# AdamOBrien_IOT2_PicController.net
KiCad netlist of a schematic drawn in EAGLE
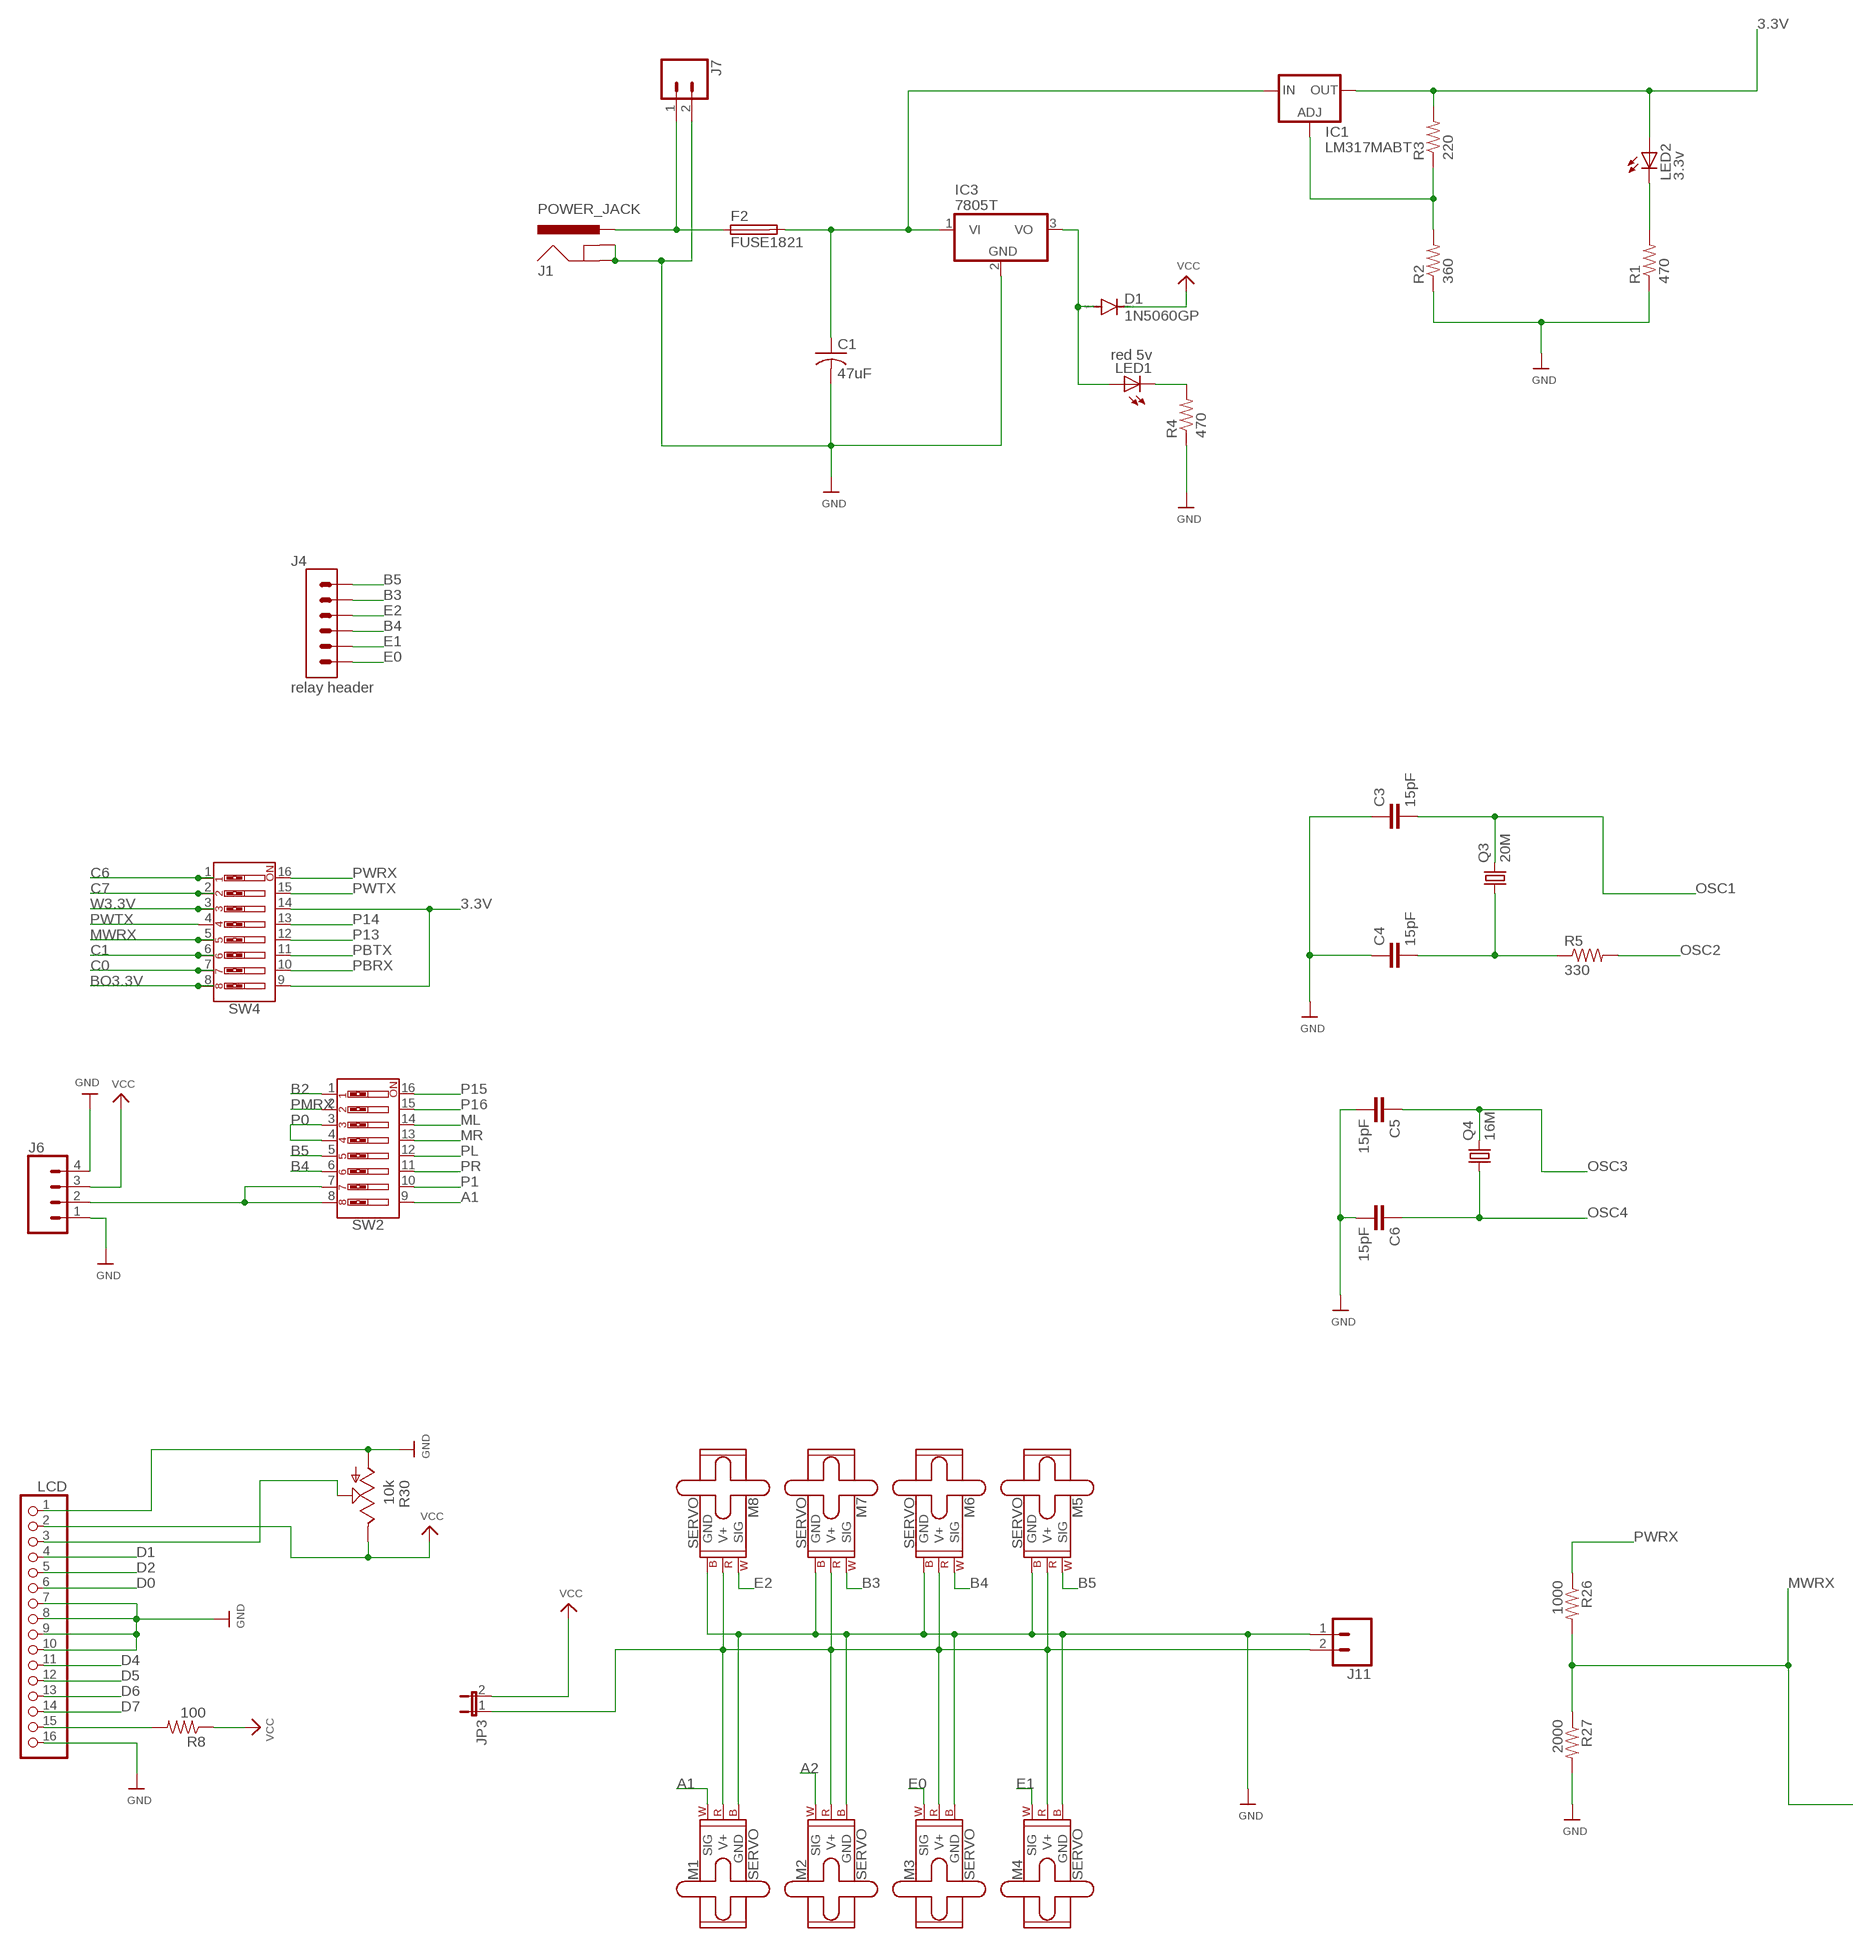
[diagram p0: schematic, sheet 1, part 1 of 2]
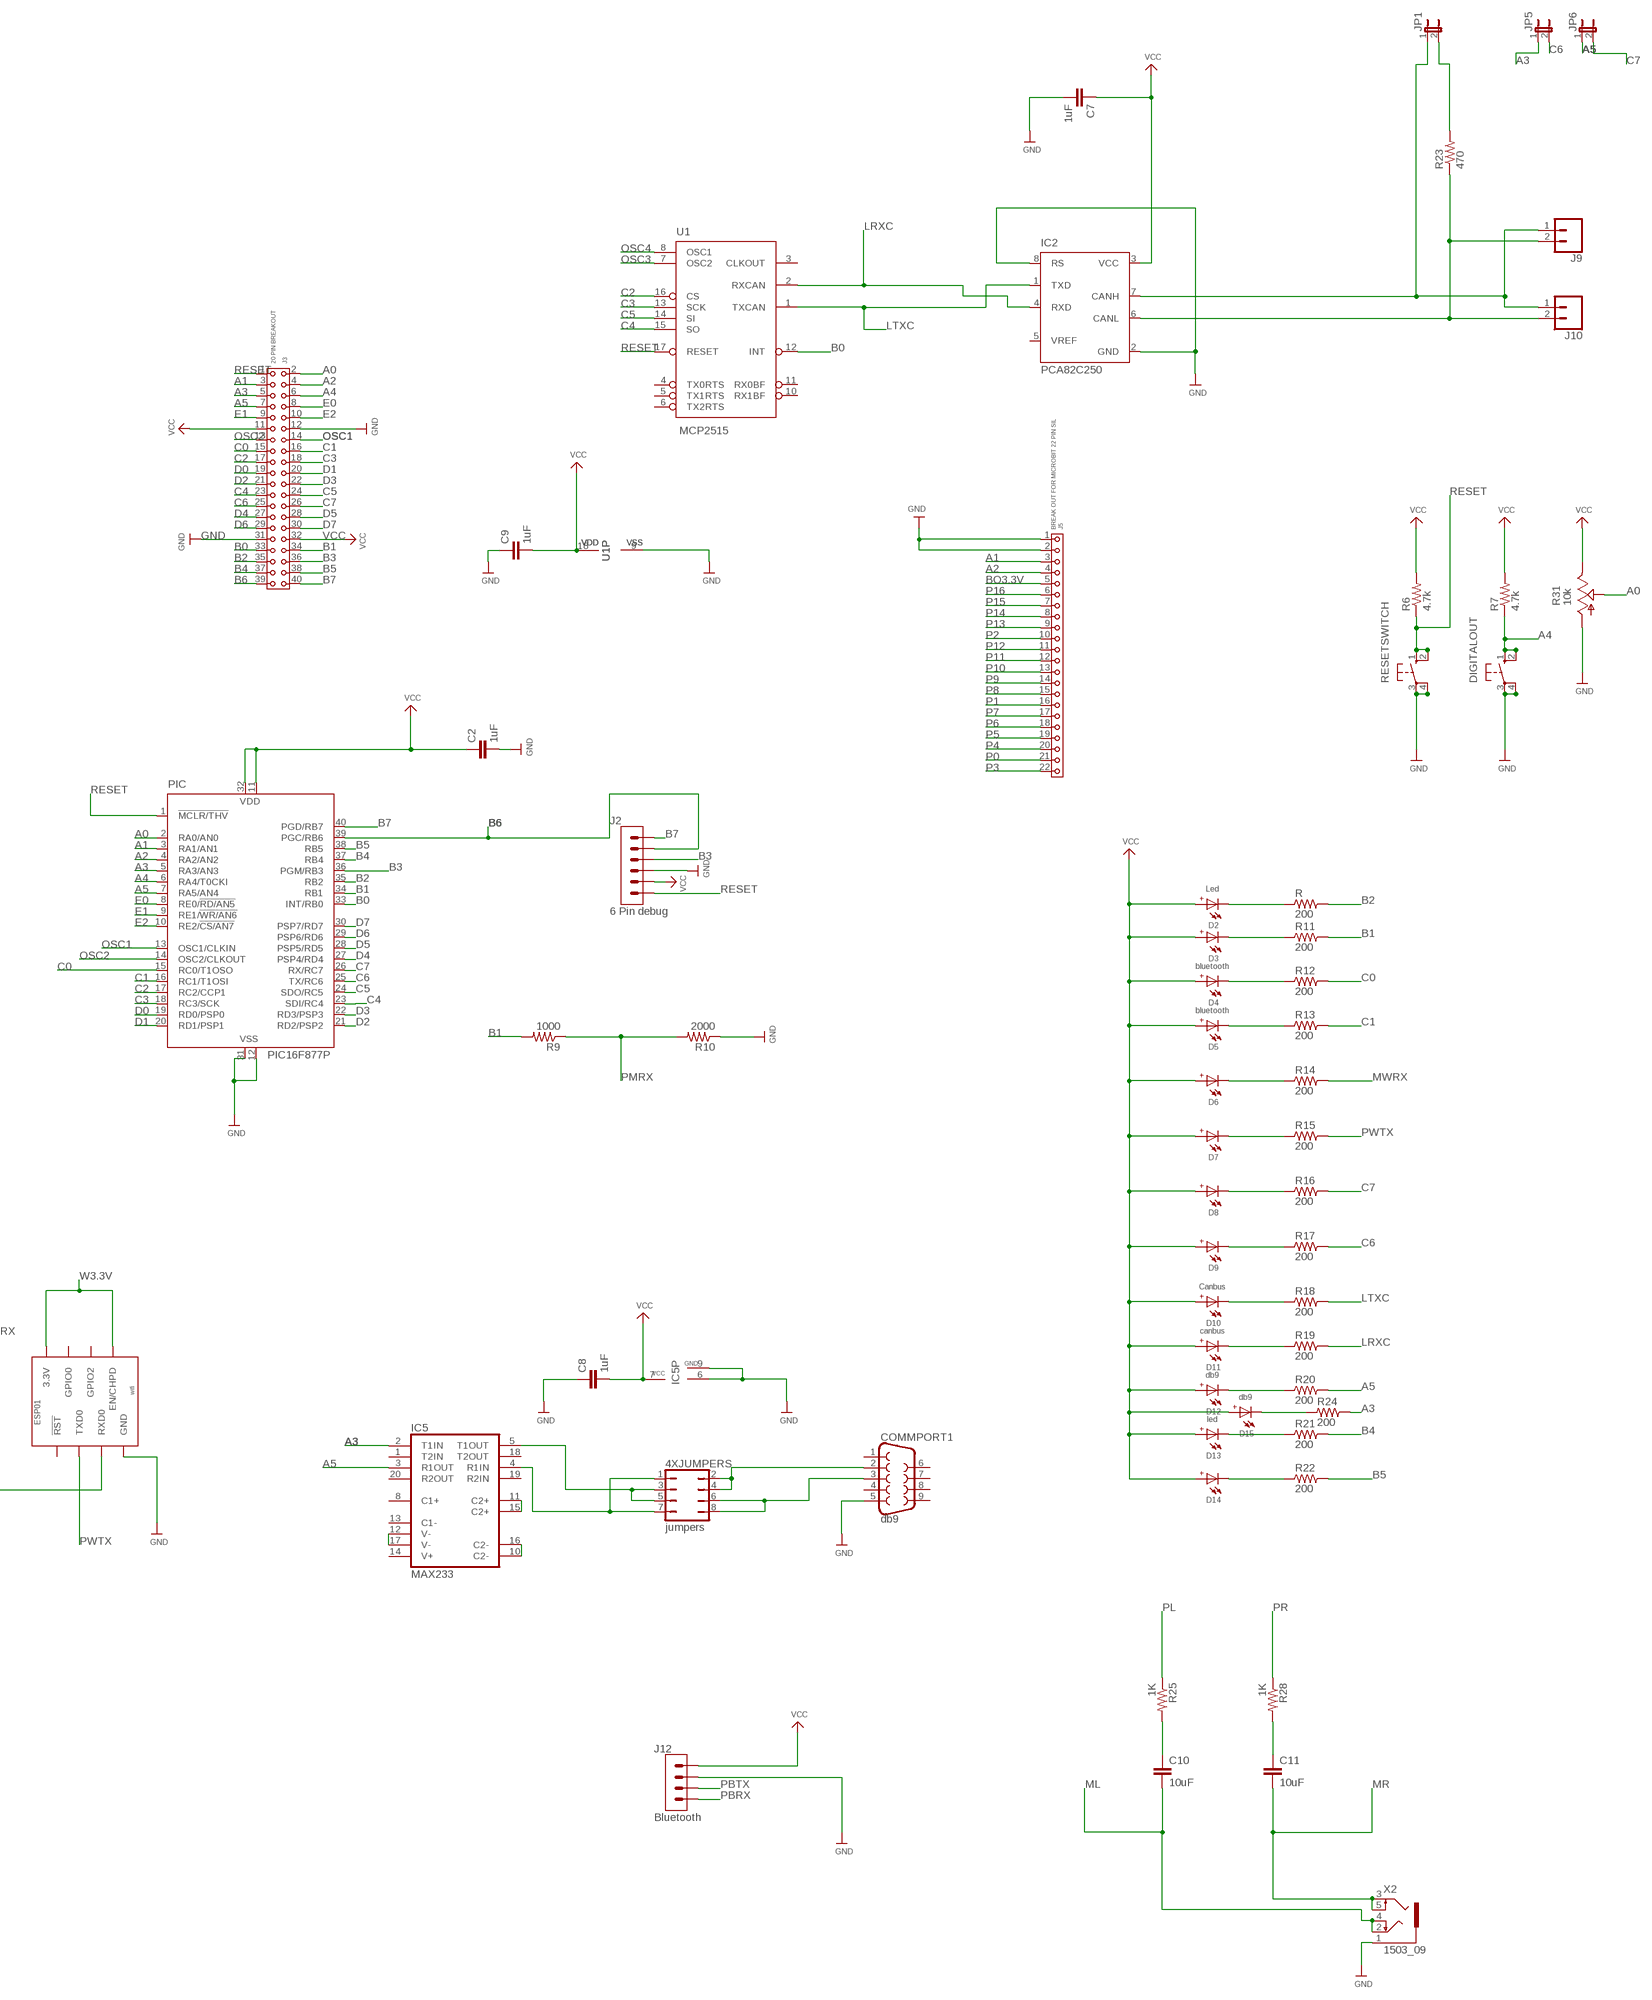
[diagram p1: schematic, sheet 1, part 2 of 2]

(export (version "E")
  (design (tool "Eeschema 10.0.6"))
  (components
    (comp (ref "4XJUMPERS")
      (value "jumpers")
      (footprint "eagle-import:JP4Q")
      (libsource (lib "eagle-import") (part "JP4Q"))
    )
    (comp (ref "C1")
      (value "47uF")
      (footprint "eagle-import:C025-024X044")
      (libsource (lib "eagle-import") (part "C-US025-024X044"))
    )
    (comp (ref "C2")
      (value "1uF")
      (footprint "eagle-import:C2.5-2")
      (libsource (lib "eagle-import") (part "C2.5/2"))
    )
    (comp (ref "C3")
      (value "15pF")
      (footprint "eagle-import:C2.5-2")
      (libsource (lib "eagle-import") (part "C2.5/2"))
    )
    (comp (ref "C4")
      (value "15pF")
      (footprint "eagle-import:C2.5-2")
      (libsource (lib "eagle-import") (part "C2.5/2"))
    )
    (comp (ref "C5")
      (value "15pF")
      (footprint "eagle-import:C2.5-2")
      (libsource (lib "eagle-import") (part "C2.5/2"))
    )
    (comp (ref "C6")
      (value "15pF")
      (footprint "eagle-import:C2.5-2")
      (libsource (lib "eagle-import") (part "C2.5/2"))
    )
    (comp (ref "C7")
      (value "1uF")
      (footprint "eagle-import:C2.5-2")
      (libsource (lib "eagle-import") (part "C2.5/2"))
    )
    (comp (ref "C8")
      (value "1uF")
      (footprint "eagle-import:C2.5-2")
      (libsource (lib "eagle-import") (part "C2.5/2"))
    )
    (comp (ref "C9")
      (value "1uF")
      (footprint "eagle-import:C2.5-2")
      (libsource (lib "eagle-import") (part "C2.5/2"))
    )
    (comp (ref "C10")
      (value "10uF")
      (footprint "eagle-import:C2.5-2")
      (libsource (lib "eagle-import") (part "C2.5/2"))
    )
    (comp (ref "C11")
      (value "10uF")
      (footprint "eagle-import:C2.5-2")
      (libsource (lib "eagle-import") (part "C2.5/2"))
    )
    (comp (ref "COMMPORT1")
      (value "db9")
      (footprint "eagle-import:DB9")
      (libsource (lib "eagle-import") (part "DB9FEMALE"))
    )
    (comp (ref "D1")
      (value "1N5060GP")
      (footprint "eagle-import:DO15-12")
      (libsource (lib "eagle-import") (part "1N5060GP"))
    )
    (comp (ref "D2")
      (value "Led")
      (footprint "eagle-import:WL-SITW_3528")
      (libsource (lib "eagle-import") (part "WL-SITW_3528_15414185BA210"))
    )
    (comp (ref "D3")
      (value "WL-SITW_3528_15414185BA210")
      (footprint "eagle-import:WL-SITW_3528")
      (libsource (lib "eagle-import") (part "WL-SITW_3528_15414185BA210"))
    )
    (comp (ref "D4")
      (value "bluetooth")
      (footprint "eagle-import:WL-SITW_3528")
      (libsource (lib "eagle-import") (part "WL-SITW_3528_15414185BA210"))
    )
    (comp (ref "D5")
      (value "bluetooth")
      (footprint "eagle-import:WL-SITW_3528")
      (libsource (lib "eagle-import") (part "WL-SITW_3528_15414185BA210"))
    )
    (comp (ref "D6")
      (value "WL-SITW_3528_15414185BA210")
      (footprint "eagle-import:WL-SITW_3528")
      (libsource (lib "eagle-import") (part "WL-SITW_3528_15414185BA210"))
    )
    (comp (ref "D7")
      (value "WL-SITW_3528_15414185BA210")
      (footprint "eagle-import:WL-SITW_3528")
      (libsource (lib "eagle-import") (part "WL-SITW_3528_15414185BA210"))
    )
    (comp (ref "D8")
      (value "WL-SITW_3528_15414185BA210")
      (footprint "eagle-import:WL-SITW_3528")
      (libsource (lib "eagle-import") (part "WL-SITW_3528_15414185BA210"))
    )
    (comp (ref "D9")
      (value "WL-SITW_3528_15414185BA210")
      (footprint "eagle-import:WL-SITW_3528")
      (libsource (lib "eagle-import") (part "WL-SITW_3528_15414185BA210"))
    )
    (comp (ref "D10")
      (value "Canbus")
      (footprint "eagle-import:WL-SITW_3528")
      (libsource (lib "eagle-import") (part "WL-SITW_3528_15414185BA210"))
    )
    (comp (ref "D11")
      (value "canbus")
      (footprint "eagle-import:WL-SITW_3528")
      (libsource (lib "eagle-import") (part "WL-SITW_3528_15414185BA210"))
    )
    (comp (ref "D12")
      (value "db9")
      (footprint "eagle-import:WL-SITW_3528")
      (libsource (lib "eagle-import") (part "WL-SITW_3528_15414185BA210"))
    )
    (comp (ref "D13")
      (value "led")
      (footprint "eagle-import:WL-SITW_3528")
      (libsource (lib "eagle-import") (part "WL-SITW_3528_15414185BA210"))
    )
    (comp (ref "D14")
      (value "WL-SITW_3528_15414185BA210")
      (footprint "eagle-import:WL-SITW_3528")
      (libsource (lib "eagle-import") (part "WL-SITW_3528_15414185BA210"))
    )
    (comp (ref "D15")
      (value "db9")
      (footprint "eagle-import:WL-SITW_3528")
      (libsource (lib "eagle-import") (part "WL-SITW_3528_15414185BA210"))
    )
    (comp (ref "DIGITALOUT")
      (value "10-XX")
      (footprint "eagle-import:B3F-10XX")
      (fields (field (name "MPN") "B3F-1000"))
      (libsource (lib "eagle-import") (part "10-XX"))
    )
    (comp (ref "ESP01")
      (value "wifi")
      (footprint "eagle-import:ESP8266_ESP-01_NO-SILKSCREEN")
      (libsource (lib "eagle-import") (part "ESP8266_ESP-?01"))
    )
    (comp (ref "F2")
      (value "FUSE1821")
      (footprint "eagle-import:FUSE_HOLDER_MENTOR-1821")
      (libsource (lib "eagle-import") (part "FUSE1821"))
    )
    (comp (ref "IC1")
      (value "LM317MABT")
      (footprint "eagle-import:TO220L1")
      (libsource (lib "eagle-import") (part "LM317?MABT"))
    )
    (comp (ref "IC2")
      (value "PCA82C250")
      (footprint "eagle-import:DIL08")
      (libsource (lib "eagle-import") (part "PCA82C250"))
    )
    (comp (ref "IC3")
      (value "7805T")
      (footprint "eagle-import:TO220H")
      (libsource (lib "eagle-import") (part "78T05"))
    )
    (comp (ref "IC5")
      (value "MAX233")
      (footprint "eagle-import:DIL20")
      (fields (field (name "MPN") "MAX233ACPP+G36"))
      (libsource (lib "eagle-import") (part "MAX233"))
    )
    (comp (ref "J1")
      (value "POWER_JACK")
      (footprint "eagle-import:POWER_JACK_PTH")
      (libsource (lib "eagle-import") (part "POWER_JACK"))
    )
    (comp (ref "J2")
      (value "6 Pin debug")
      (footprint "eagle-import:62000611121")
      (fields
        (field (name "MANUFACTURER") "Würth Elektronik ")
        (field (name "MPN") "62000611121")
        (field (name "CREATED_BY") "PCBLayout.com")
      )
      (libsource (lib "eagle-import") (part "62000611121"))
    )
    (comp (ref "J3")
      (value "20 PIN BREAKOUT")
      (footprint "eagle-import:61304021821")
      (libsource (lib "eagle-import") (part "6130XX21821_61304021821"))
    )
    (comp (ref "J4")
      (value "relay header")
      (footprint "eagle-import:62000611121")
      (fields
        (field (name "MANUFACTURER") "Würth Elektronik ")
        (field (name "MPN") "62000611121")
        (field (name "CREATED_BY") "PCBLayout.com")
      )
      (libsource (lib "eagle-import") (part "62000611121"))
    )
    (comp (ref "J5")
      (value "BREAK OUT FOR MICROBIT 22 PIN SIL")
      (footprint "eagle-import:61302211821")
      (libsource (lib "eagle-import") (part "6130XX11821_61302211821"))
    )
    (comp (ref "J6")
      (value "CONN_04")
      (footprint "eagle-import:1X04")
      (libsource (lib "eagle-import") (part "CONN_04"))
    )
    (comp (ref "J7")
      (value "CONN_025MM")
      (footprint "eagle-import:SCREWTERMINAL-5MM-2")
      (libsource (lib "eagle-import") (part "CONN_025MM"))
    )
    (comp (ref "J9")
      (value "CONN_025MM")
      (footprint "eagle-import:SCREWTERMINAL-5MM-2")
      (libsource (lib "eagle-import") (part "CONN_025MM"))
    )
    (comp (ref "J10")
      (value "CONN_025MM")
      (footprint "eagle-import:SCREWTERMINAL-5MM-2")
      (libsource (lib "eagle-import") (part "CONN_025MM"))
    )
    (comp (ref "J11")
      (value "CONN_025MM")
      (footprint "eagle-import:SCREWTERMINAL-5MM-2")
      (libsource (lib "eagle-import") (part "CONN_025MM"))
    )
    (comp (ref "J12")
      (value "Bluetooth")
      (footprint "eagle-import:62000411121")
      (fields
        (field (name "MANUFACTURER") "Würth Elektronik ")
        (field (name "MPN") "62000411121")
        (field (name "CREATED_BY") "PCBLayout.com")
      )
      (libsource (lib "eagle-import") (part "62000411121"))
    )
    (comp (ref "JP1")
      (value "JP1E")
      (footprint "eagle-import:JP1")
      (libsource (lib "eagle-import") (part "JP1E"))
    )
    (comp (ref "JP3")
      (value "JP1E")
      (footprint "eagle-import:JP1")
      (libsource (lib "eagle-import") (part "JP1E"))
    )
    (comp (ref "JP5")
      (value "JP1E")
      (footprint "eagle-import:JP1")
      (libsource (lib "eagle-import") (part "JP1E"))
    )
    (comp (ref "JP6")
      (value "JP1E")
      (footprint "eagle-import:JP1")
      (libsource (lib "eagle-import") (part "JP1E"))
    )
    (comp (ref "LCD")
      (value "PINHD-1X16")
      (footprint "eagle-import:1X16")
      (libsource (lib "eagle-import") (part "PINHD-1X16"))
    )
    (comp (ref "LED1")
      (value "red 5v")
      (footprint "eagle-import:LED5MM")
      (libsource (lib "eagle-import") (part "LED5MM"))
    )
    (comp (ref "LED2")
      (value "3.3v")
      (footprint "eagle-import:LED5MM")
      (libsource (lib "eagle-import") (part "LED5MM"))
    )
    (comp (ref "M1")
      (value "SERVO")
      (footprint "eagle-import:1X03")
      (libsource (lib "eagle-import") (part "SERVO"))
    )
    (comp (ref "M2")
      (value "SERVO")
      (footprint "eagle-import:1X03")
      (libsource (lib "eagle-import") (part "SERVO"))
    )
    (comp (ref "M3")
      (value "SERVO")
      (footprint "eagle-import:1X03")
      (libsource (lib "eagle-import") (part "SERVO"))
    )
    (comp (ref "M4")
      (value "SERVO")
      (footprint "eagle-import:1X03")
      (libsource (lib "eagle-import") (part "SERVO"))
    )
    (comp (ref "M5")
      (value "SERVO")
      (footprint "eagle-import:1X03")
      (libsource (lib "eagle-import") (part "SERVO"))
    )
    (comp (ref "M6")
      (value "SERVO")
      (footprint "eagle-import:1X03")
      (libsource (lib "eagle-import") (part "SERVO"))
    )
    (comp (ref "M7")
      (value "SERVO")
      (footprint "eagle-import:1X03")
      (libsource (lib "eagle-import") (part "SERVO"))
    )
    (comp (ref "M8")
      (value "SERVO")
      (footprint "eagle-import:1X03")
      (libsource (lib "eagle-import") (part "SERVO"))
    )
    (comp (ref "PIC")
      (value "PIC16F877P")
      (footprint "eagle-import:DIL40")
      (fields (field (name "MF") "MICROCHIP") (field (name "MPN") "PIC16F877-04/P"))
      (libsource (lib "eagle-import") (part "PIC16F87P7"))
    )
    (comp (ref "Q3")
      (value "20M")
      (footprint "eagle-import:HC49_S")
      (libsource (lib "eagle-import") (part "CRYSTALHC49S"))
    )
    (comp (ref "Q4")
      (value "16M")
      (footprint "eagle-import:HC49_S")
      (libsource (lib "eagle-import") (part "CRYSTALHC49S"))
    )
    (comp (ref "R")
      (value "200")
      (footprint "eagle-import:RC-MASTER-SMD_R1206MP")
      (libsource (lib "eagle-import") (part "RC-MASTER-SMD_R_1206MP"))
    )
    (comp (ref "R1")
      (value "470")
      (footprint "eagle-import:0204_7")
      (libsource (lib "eagle-import") (part "R-US_0204/7"))
    )
    (comp (ref "R2")
      (value "360")
      (footprint "eagle-import:0204_7")
      (libsource (lib "eagle-import") (part "R-US_0204/7"))
    )
    (comp (ref "R3")
      (value "220")
      (footprint "eagle-import:0204_7")
      (libsource (lib "eagle-import") (part "R-US_0204/7"))
    )
    (comp (ref "R4")
      (value "470")
      (footprint "eagle-import:0204_7")
      (libsource (lib "eagle-import") (part "R-US_0204/7"))
    )
    (comp (ref "R5")
      (value "330")
      (footprint "eagle-import:0204_7")
      (libsource (lib "eagle-import") (part "R-US_0204/7"))
    )
    (comp (ref "R6")
      (value "4.7k")
      (footprint "eagle-import:0204_7")
      (libsource (lib "eagle-import") (part "R-US_0204/7"))
    )
    (comp (ref "R7")
      (value "4.7k")
      (footprint "eagle-import:0204_7")
      (libsource (lib "eagle-import") (part "R-US_0204/7"))
    )
    (comp (ref "R8")
      (value "100")
      (footprint "eagle-import:0204_7")
      (libsource (lib "eagle-import") (part "R-US_0204/7"))
    )
    (comp (ref "R9")
      (value "1000")
      (footprint "eagle-import:0204_7")
      (libsource (lib "eagle-import") (part "R-US_0204/7"))
    )
    (comp (ref "R10")
      (value "2000")
      (footprint "eagle-import:0204_7")
      (libsource (lib "eagle-import") (part "R-US_0204/7"))
    )
    (comp (ref "R11")
      (value "200")
      (footprint "eagle-import:RC-MASTER-SMD_R1206MP")
      (libsource (lib "eagle-import") (part "RC-MASTER-SMD_R_1206MP"))
    )
    (comp (ref "R12")
      (value "200")
      (footprint "eagle-import:RC-MASTER-SMD_R1206MP")
      (libsource (lib "eagle-import") (part "RC-MASTER-SMD_R_1206MP"))
    )
    (comp (ref "R13")
      (value "200")
      (footprint "eagle-import:RC-MASTER-SMD_R1206MP")
      (libsource (lib "eagle-import") (part "RC-MASTER-SMD_R_1206MP"))
    )
    (comp (ref "R14")
      (value "200")
      (footprint "eagle-import:RC-MASTER-SMD_R1206MP")
      (libsource (lib "eagle-import") (part "RC-MASTER-SMD_R_1206MP"))
    )
    (comp (ref "R15")
      (value "200")
      (footprint "eagle-import:RC-MASTER-SMD_R1206MP")
      (libsource (lib "eagle-import") (part "RC-MASTER-SMD_R_1206MP"))
    )
    (comp (ref "R16")
      (value "200")
      (footprint "eagle-import:RC-MASTER-SMD_R1206MP")
      (libsource (lib "eagle-import") (part "RC-MASTER-SMD_R_1206MP"))
    )
    (comp (ref "R17")
      (value "200")
      (footprint "eagle-import:RC-MASTER-SMD_R1206MP")
      (libsource (lib "eagle-import") (part "RC-MASTER-SMD_R_1206MP"))
    )
    (comp (ref "R18")
      (value "200")
      (footprint "eagle-import:RC-MASTER-SMD_R1206MP")
      (libsource (lib "eagle-import") (part "RC-MASTER-SMD_R_1206MP"))
    )
    (comp (ref "R19")
      (value "200")
      (footprint "eagle-import:RC-MASTER-SMD_R1206MP")
      (libsource (lib "eagle-import") (part "RC-MASTER-SMD_R_1206MP"))
    )
    (comp (ref "R20")
      (value "200")
      (footprint "eagle-import:RC-MASTER-SMD_R1206MP")
      (libsource (lib "eagle-import") (part "RC-MASTER-SMD_R_1206MP"))
    )
    (comp (ref "R21")
      (value "200")
      (footprint "eagle-import:RC-MASTER-SMD_R1206MP")
      (libsource (lib "eagle-import") (part "RC-MASTER-SMD_R_1206MP"))
    )
    (comp (ref "R22")
      (value "200")
      (footprint "eagle-import:RC-MASTER-SMD_R1206MP")
      (libsource (lib "eagle-import") (part "RC-MASTER-SMD_R_1206MP"))
    )
    (comp (ref "R23")
      (value "470")
      (footprint "eagle-import:0204_7")
      (libsource (lib "eagle-import") (part "R-US_0204/7"))
    )
    (comp (ref "R24")
      (value "200")
      (footprint "eagle-import:RC-MASTER-SMD_R1206MP")
      (libsource (lib "eagle-import") (part "RC-MASTER-SMD_R_1206MP"))
    )
    (comp (ref "R25")
      (value "1K")
      (footprint "eagle-import:0204_7")
      (libsource (lib "eagle-import") (part "R-US_0204/7"))
    )
    (comp (ref "R26")
      (value "1000")
      (footprint "eagle-import:0204_7")
      (libsource (lib "eagle-import") (part "R-US_0204/7"))
    )
    (comp (ref "R27")
      (value "2000")
      (footprint "eagle-import:0204_7")
      (libsource (lib "eagle-import") (part "R-US_0204/7"))
    )
    (comp (ref "R28")
      (value "1K")
      (footprint "eagle-import:0204_7")
      (libsource (lib "eagle-import") (part "R-US_0204/7"))
    )
    (comp (ref "R30")
      (value "10k")
      (footprint "eagle-import:RS3")
      (libsource (lib "eagle-import") (part "TRIM_US-RS3"))
    )
    (comp (ref "R31")
      (value "10k")
      (footprint "eagle-import:RS3")
      (libsource (lib "eagle-import") (part "TRIM_US-RS3"))
    )
    (comp (ref "RESETSWITCH")
      (value "10-XX")
      (footprint "eagle-import:B3F-10XX")
      (fields (field (name "MPN") "B3F-1000"))
      (libsource (lib "eagle-import") (part "10-XX"))
    )
    (comp (ref "SW2")
      (value "DIP-08-PTH")
      (footprint "eagle-import:DIPSWITCH-08")
      (libsource (lib "eagle-import") (part "DIP-08-PTH"))
    )
    (comp (ref "SW4")
      (value "DIP-08-PTH")
      (footprint "eagle-import:DIPSWITCH-08")
      (libsource (lib "eagle-import") (part "DIP-08-PTH"))
    )
    (comp (ref "U1")
      (value "MCP2515")
      (footprint "eagle-import:DIP18")
      (libsource (lib "eagle-import") (part "MCP2515(MCP2510)P"))
    )
    (comp (ref "X2")
      (value "1503_09")
      (footprint "eagle-import:1503_09")
      (libsource (lib "eagle-import") (part "1503_09"))
    )
  )
  (nets
    (net (code "1") (name "3.3V") (class "Default")
      (node (ref "IC1") (pin "2") (pinfunction "OUT_2") (pintype "passive"))
      (node (ref "LED2") (pin "A") (pinfunction "A_A") (pintype "passive"))
      (node (ref "R3") (pin "2") (pinfunction "2_2") (pintype "passive"))
      (node (ref "SW4") (pin "14") (pinfunction "14_14") (pintype "passive"))
      (node (ref "SW4") (pin "9") (pinfunction "9_9") (pintype "passive"))
    )
    (net (code "2") (name "A0") (class "Default")
      (node (ref "J3") (pin "2") (pinfunction "2_2") (pintype "passive"))
      (node (ref "PIC") (pin "2") (pinfunction "RA0/AN0_2") (pintype "bidirectional"))
      (node (ref "R31") (pin "S") (pinfunction "S_S") (pintype "passive"))
    )
    (net (code "3") (name "A1") (class "Default")
      (node (ref "J3") (pin "3") (pinfunction "3_3") (pintype "passive"))
      (node (ref "J5") (pin "3") (pinfunction "3_3") (pintype "passive"))
      (node (ref "M1") (pin "1") (pinfunction "SIG_1") (pintype "bidirectional"))
      (node (ref "PIC") (pin "3") (pinfunction "RA1/AN1_3") (pintype "bidirectional"))
      (node (ref "SW2") (pin "9") (pinfunction "9_9") (pintype "passive"))
    )
    (net (code "4") (name "A2") (class "Default")
      (node (ref "J3") (pin "4") (pinfunction "4_4") (pintype "passive"))
      (node (ref "J5") (pin "4") (pinfunction "4_4") (pintype "passive"))
      (node (ref "M2") (pin "1") (pinfunction "SIG_1") (pintype "bidirectional"))
      (node (ref "PIC") (pin "4") (pinfunction "RA2/AN2_4") (pintype "bidirectional"))
    )
    (net (code "5") (name "A3") (class "Default")
      (node (ref "IC5") (pin "2") (pinfunction "T1IN_2") (pintype "input"))
      (node (ref "J3") (pin "5") (pinfunction "5_5") (pintype "passive"))
      (node (ref "JP5") (pin "1") (pinfunction "1_1") (pintype "passive"))
      (node (ref "PIC") (pin "5") (pinfunction "RA3/AN3_5") (pintype "bidirectional"))
      (node (ref "R24") (pin "2") (pinfunction "2_2") (pintype "passive"))
    )
    (net (code "6") (name "A4") (class "Default")
      (node (ref "DIGITALOUT") (pin "1") (pinfunction "S_1") (pintype "passive"))
      (node (ref "DIGITALOUT") (pin "2") (pinfunction "S1_2") (pintype "passive"))
      (node (ref "J3") (pin "6") (pinfunction "6_6") (pintype "passive"))
      (node (ref "PIC") (pin "6") (pinfunction "RA4/T0CKI_6") (pintype "bidirectional"))
      (node (ref "R7") (pin "1") (pinfunction "1_1") (pintype "passive"))
    )
    (net (code "7") (name "A5") (class "Default")
      (node (ref "IC5") (pin "3") (pinfunction "R1OUT_3") (pintype "output"))
      (node (ref "J3") (pin "7") (pinfunction "7_7") (pintype "passive"))
      (node (ref "JP6") (pin "1") (pinfunction "1_1") (pintype "passive"))
      (node (ref "PIC") (pin "7") (pinfunction "RA5/AN4_7") (pintype "bidirectional"))
      (node (ref "R20") (pin "2") (pinfunction "2_2") (pintype "passive"))
    )
    (net (code "8") (name "B0") (class "Default")
      (node (ref "J3") (pin "33") (pinfunction "33_33") (pintype "passive"))
      (node (ref "PIC") (pin "33") (pinfunction "INT/RB0_33") (pintype "bidirectional"))
      (node (ref "U1") (pin "12") (pinfunction "INT_12") (pintype "output"))
    )
    (net (code "9") (name "B1") (class "Default")
      (node (ref "J3") (pin "34") (pinfunction "34_34") (pintype "passive"))
      (node (ref "PIC") (pin "34") (pinfunction "RB1_34") (pintype "bidirectional"))
      (node (ref "R11") (pin "2") (pinfunction "2_2") (pintype "passive"))
      (node (ref "R9") (pin "2") (pinfunction "2_2") (pintype "passive"))
    )
    (net (code "10") (name "B2") (class "Default")
      (node (ref "J3") (pin "35") (pinfunction "35_35") (pintype "passive"))
      (node (ref "PIC") (pin "35") (pinfunction "RB2_35") (pintype "bidirectional"))
      (node (ref "R") (pin "2") (pinfunction "2_2") (pintype "passive"))
      (node (ref "SW2") (pin "1") (pinfunction "1_1") (pintype "passive"))
    )
    (net (code "11") (name "B3") (class "Default")
      (node (ref "J2") (pin "3") (pinfunction "3_3") (pintype "passive"))
      (node (ref "J3") (pin "36") (pinfunction "36_36") (pintype "passive"))
      (node (ref "J4") (pin "2") (pinfunction "2_2") (pintype "passive"))
      (node (ref "M7") (pin "1") (pinfunction "SIG_1") (pintype "bidirectional"))
      (node (ref "PIC") (pin "36") (pinfunction "PGM/RB3_36") (pintype "bidirectional"))
    )
    (net (code "12") (name "B4") (class "Default")
      (node (ref "J3") (pin "37") (pinfunction "37_37") (pintype "passive"))
      (node (ref "J4") (pin "4") (pinfunction "4_4") (pintype "passive"))
      (node (ref "M6") (pin "1") (pinfunction "SIG_1") (pintype "bidirectional"))
      (node (ref "PIC") (pin "37") (pinfunction "RB4_37") (pintype "bidirectional"))
      (node (ref "R21") (pin "2") (pinfunction "2_2") (pintype "passive"))
      (node (ref "SW2") (pin "6") (pinfunction "6_6") (pintype "passive"))
    )
    (net (code "13") (name "B5") (class "Default")
      (node (ref "J3") (pin "38") (pinfunction "38_38") (pintype "passive"))
      (node (ref "J4") (pin "1") (pinfunction "1_1") (pintype "passive"))
      (node (ref "M5") (pin "1") (pinfunction "SIG_1") (pintype "bidirectional"))
      (node (ref "PIC") (pin "38") (pinfunction "RB5_38") (pintype "bidirectional"))
      (node (ref "R22") (pin "2") (pinfunction "2_2") (pintype "passive"))
      (node (ref "SW2") (pin "5") (pinfunction "5_5") (pintype "passive"))
    )
    (net (code "14") (name "B6") (class "Default")
      (node (ref "J2") (pin "2") (pinfunction "2_2") (pintype "passive"))
      (node (ref "J3") (pin "39") (pinfunction "39_39") (pintype "passive"))
      (node (ref "PIC") (pin "39") (pinfunction "PGC/RB6_39") (pintype "bidirectional"))
    )
    (net (code "15") (name "B7") (class "Default")
      (node (ref "J2") (pin "1") (pinfunction "1_1") (pintype "passive"))
      (node (ref "J3") (pin "40") (pinfunction "40_40") (pintype "passive"))
      (node (ref "PIC") (pin "40") (pinfunction "PGD/RB7_40") (pintype "bidirectional"))
    )
    (net (code "16") (name "BO3.3V") (class "Default")
      (node (ref "J5") (pin "5") (pinfunction "5_5") (pintype "passive"))
      (node (ref "SW4") (pin "8") (pinfunction "8_8") (pintype "passive"))
    )
    (net (code "17") (name "C0") (class "Default")
      (node (ref "J3") (pin "15") (pinfunction "15_15") (pintype "passive"))
      (node (ref "PIC") (pin "15") (pinfunction "RC0/T1OSO_15") (pintype "bidirectional"))
      (node (ref "R12") (pin "2") (pinfunction "2_2") (pintype "passive"))
      (node (ref "SW4") (pin "7") (pinfunction "7_7") (pintype "passive"))
    )
    (net (code "18") (name "C1") (class "Default")
      (node (ref "J3") (pin "16") (pinfunction "16_16") (pintype "passive"))
      (node (ref "PIC") (pin "16") (pinfunction "RC1/T1OSI_16") (pintype "bidirectional"))
      (node (ref "R13") (pin "2") (pinfunction "2_2") (pintype "passive"))
      (node (ref "SW4") (pin "6") (pinfunction "6_6") (pintype "passive"))
    )
    (net (code "19") (name "C2") (class "Default")
      (node (ref "J3") (pin "17") (pinfunction "17_17") (pintype "passive"))
      (node (ref "PIC") (pin "17") (pinfunction "RC2/CCP1_17") (pintype "bidirectional"))
      (node (ref "U1") (pin "16") (pinfunction "CS_16") (pintype "input"))
    )
    (net (code "20") (name "C3") (class "Default")
      (node (ref "J3") (pin "18") (pinfunction "18_18") (pintype "passive"))
      (node (ref "PIC") (pin "18") (pinfunction "RC3/SCK_18") (pintype "bidirectional"))
      (node (ref "U1") (pin "13") (pinfunction "SCK_13") (pintype "input"))
    )
    (net (code "21") (name "C4") (class "Default")
      (node (ref "J3") (pin "23") (pinfunction "23_23") (pintype "passive"))
      (node (ref "PIC") (pin "23") (pinfunction "SDI/RC4_23") (pintype "bidirectional"))
      (node (ref "U1") (pin "15") (pinfunction "SO_15") (pintype "output"))
    )
    (net (code "22") (name "C5") (class "Default")
      (node (ref "J3") (pin "24") (pinfunction "24_24") (pintype "passive"))
      (node (ref "PIC") (pin "24") (pinfunction "SDO/RC5_24") (pintype "bidirectional"))
      (node (ref "U1") (pin "14") (pinfunction "SI_14") (pintype "input"))
    )
    (net (code "23") (name "C6") (class "Default")
      (node (ref "J3") (pin "25") (pinfunction "25_25") (pintype "passive"))
      (node (ref "JP5") (pin "2") (pinfunction "2_2") (pintype "passive"))
      (node (ref "PIC") (pin "25") (pinfunction "TX/RC6_25") (pintype "bidirectional"))
      (node (ref "R17") (pin "2") (pinfunction "2_2") (pintype "passive"))
      (node (ref "SW4") (pin "1") (pinfunction "1_1") (pintype "passive"))
    )
    (net (code "24") (name "C7") (class "Default")
      (node (ref "J3") (pin "26") (pinfunction "26_26") (pintype "passive"))
      (node (ref "JP6") (pin "2") (pinfunction "2_2") (pintype "passive"))
      (node (ref "PIC") (pin "26") (pinfunction "RX/RC7_26") (pintype "bidirectional"))
      (node (ref "R16") (pin "2") (pinfunction "2_2") (pintype "passive"))
      (node (ref "SW4") (pin "2") (pinfunction "2_2") (pintype "passive"))
    )
    (net (code "25") (name "D0") (class "Default")
      (node (ref "J3") (pin "19") (pinfunction "19_19") (pintype "passive"))
      (node (ref "LCD") (pin "6") (pinfunction "6_6") (pintype "passive"))
      (node (ref "PIC") (pin "19") (pinfunction "RD0/PSP0_19") (pintype "bidirectional"))
    )
    (net (code "26") (name "D1") (class "Default")
      (node (ref "J3") (pin "20") (pinfunction "20_20") (pintype "passive"))
      (node (ref "LCD") (pin "4") (pinfunction "4_4") (pintype "passive"))
      (node (ref "PIC") (pin "20") (pinfunction "RD1/PSP1_20") (pintype "bidirectional"))
    )
    (net (code "27") (name "D2") (class "Default")
      (node (ref "J3") (pin "21") (pinfunction "21_21") (pintype "passive"))
      (node (ref "LCD") (pin "5") (pinfunction "5_5") (pintype "passive"))
      (node (ref "PIC") (pin "21") (pinfunction "RD2/PSP2_21") (pintype "bidirectional"))
    )
    (net (code "28") (name "D3") (class "Default")
      (node (ref "J3") (pin "22") (pinfunction "22_22") (pintype "passive"))
      (node (ref "PIC") (pin "22") (pinfunction "RD3/PSP3_22") (pintype "bidirectional"))
    )
    (net (code "29") (name "D4") (class "Default")
      (node (ref "J3") (pin "27") (pinfunction "27_27") (pintype "passive"))
      (node (ref "LCD") (pin "11") (pinfunction "11_11") (pintype "passive"))
      (node (ref "PIC") (pin "27") (pinfunction "PSP4/RD4_27") (pintype "bidirectional"))
    )
    (net (code "30") (name "D5") (class "Default")
      (node (ref "J3") (pin "28") (pinfunction "28_28") (pintype "passive"))
      (node (ref "LCD") (pin "12") (pinfunction "12_12") (pintype "passive"))
      (node (ref "PIC") (pin "28") (pinfunction "PSP5/RD5_28") (pintype "bidirectional"))
    )
    (net (code "31") (name "D6") (class "Default")
      (node (ref "J3") (pin "29") (pinfunction "29_29") (pintype "passive"))
      (node (ref "LCD") (pin "13") (pinfunction "13_13") (pintype "passive"))
      (node (ref "PIC") (pin "29") (pinfunction "PSP6/RD6_29") (pintype "bidirectional"))
    )
    (net (code "32") (name "D7") (class "Default")
      (node (ref "J3") (pin "30") (pinfunction "30_30") (pintype "passive"))
      (node (ref "LCD") (pin "14") (pinfunction "14_14") (pintype "passive"))
      (node (ref "PIC") (pin "30") (pinfunction "PSP7/RD7_30") (pintype "bidirectional"))
    )
    (net (code "33") (name "E0") (class "Default")
      (node (ref "J3") (pin "8") (pinfunction "8_8") (pintype "passive"))
      (node (ref "J4") (pin "6") (pinfunction "6_6") (pintype "passive"))
      (node (ref "M3") (pin "1") (pinfunction "SIG_1") (pintype "bidirectional"))
      (node (ref "PIC") (pin "8") (pinfunction "RE0/~{RD/AN5}_8") (pintype "bidirectional"))
    )
    (net (code "34") (name "E1") (class "Default")
      (node (ref "J3") (pin "9") (pinfunction "9_9") (pintype "passive"))
      (node (ref "J4") (pin "5") (pinfunction "5_5") (pintype "passive"))
      (node (ref "M4") (pin "1") (pinfunction "SIG_1") (pintype "bidirectional"))
      (node (ref "PIC") (pin "9") (pinfunction "RE1/~{WR/AN6}_9") (pintype "bidirectional"))
    )
    (net (code "35") (name "E2") (class "Default")
      (node (ref "J3") (pin "10") (pinfunction "10_10") (pintype "passive"))
      (node (ref "J4") (pin "3") (pinfunction "3_3") (pintype "passive"))
      (node (ref "M8") (pin "1") (pinfunction "SIG_1") (pintype "bidirectional"))
      (node (ref "PIC") (pin "10") (pinfunction "RE2/~{CS/AN7}_10") (pintype "bidirectional"))
    )
    (net (code "36") (name "GND") (class "Default")
      (node (ref "C1") (pin "2") (pinfunction "2_2") (pintype "passive"))
      (node (ref "C2") (pin "2") (pinfunction "2_2") (pintype "passive"))
      (node (ref "C3") (pin "1") (pinfunction "1_1") (pintype "passive"))
      (node (ref "C4") (pin "1") (pinfunction "1_1") (pintype "passive"))
      (node (ref "C5") (pin "2") (pinfunction "2_2") (pintype "passive"))
      (node (ref "C6") (pin "2") (pinfunction "2_2") (pintype "passive"))
      (node (ref "C7") (pin "2") (pinfunction "2_2") (pintype "passive"))
      (node (ref "C8") (pin "1") (pinfunction "1_1") (pintype "passive"))
      (node (ref "C9") (pin "1") (pinfunction "1_1") (pintype "passive"))
      (node (ref "COMMPORT1") (pin "5") (pinfunction "5_5") (pintype "passive"))
      (node (ref "DIGITALOUT") (pin "3") (pinfunction "P_3") (pintype "passive"))
      (node (ref "DIGITALOUT") (pin "4") (pinfunction "P1_4") (pintype "passive"))
      (node (ref "ESP01") (pin "GND") (pinfunction "GND_GND") (pintype "passive"))
      (node (ref "IC2") (pin "2") (pinfunction "GND_2") (pintype "power_in"))
      (node (ref "IC2") (pin "8") (pinfunction "RS_8") (pintype "input"))
      (node (ref "IC3") (pin "2") (pinfunction "GND_2") (pintype "passive"))
      (node (ref "IC5") (pin "6") (pinfunction "GND_6") (pintype "power_in"))
      (node (ref "IC5") (pin "9") (pinfunction "GND_9") (pintype "power_in"))
      (node (ref "J1") (pin "GND") (pinfunction "GND_GND") (pintype "bidirectional"))
      (node (ref "J1") (pin "GNDBREAK") (pinfunction "GNDBREAK_GNDBREAK") (pintype "bidirectional"))
      (node (ref "J11") (pin "1") (pinfunction "1_1") (pintype "passive"))
      (node (ref "J12") (pin "2") (pinfunction "2_2") (pintype "passive"))
      (node (ref "J2") (pin "4") (pinfunction "4_4") (pintype "passive"))
      (node (ref "J3") (pin "12") (pinfunction "12_12") (pintype "passive"))
      (node (ref "J3") (pin "31") (pinfunction "31_31") (pintype "passive"))
      (node (ref "J5") (pin "1") (pinfunction "1_1") (pintype "passive"))
      (node (ref "J5") (pin "2") (pinfunction "2_2") (pintype "passive"))
      (node (ref "J6") (pin "1") (pinfunction "1_1") (pintype "passive"))
      (node (ref "J6") (pin "4") (pinfunction "4_4") (pintype "passive"))
      (node (ref "J7") (pin "2") (pinfunction "2_2") (pintype "passive"))
      (node (ref "LCD") (pin "1") (pinfunction "1_1") (pintype "passive"))
      (node (ref "LCD") (pin "10") (pinfunction "10_10") (pintype "passive"))
      (node (ref "LCD") (pin "16") (pinfunction "16_16") (pintype "passive"))
      (node (ref "LCD") (pin "7") (pinfunction "7_7") (pintype "passive"))
      (node (ref "LCD") (pin "8") (pinfunction "8_8") (pintype "passive"))
      (node (ref "LCD") (pin "9") (pinfunction "9_9") (pintype "passive"))
      (node (ref "M1") (pin "3") (pinfunction "GND_3") (pintype "bidirectional"))
      (node (ref "M2") (pin "3") (pinfunction "GND_3") (pintype "bidirectional"))
      (node (ref "M3") (pin "3") (pinfunction "GND_3") (pintype "bidirectional"))
      (node (ref "M4") (pin "3") (pinfunction "GND_3") (pintype "bidirectional"))
      (node (ref "M5") (pin "3") (pinfunction "GND_3") (pintype "bidirectional"))
      (node (ref "M6") (pin "3") (pinfunction "GND_3") (pintype "bidirectional"))
      (node (ref "M7") (pin "3") (pinfunction "GND_3") (pintype "bidirectional"))
      (node (ref "M8") (pin "3") (pinfunction "GND_3") (pintype "bidirectional"))
      (node (ref "PIC") (pin "12") (pinfunction "VSS_12") (pintype "power_in"))
      (node (ref "PIC") (pin "31") (pinfunction "VSS_31") (pintype "power_in"))
      (node (ref "R1") (pin "1") (pinfunction "1_1") (pintype "passive"))
      (node (ref "R10") (pin "1") (pinfunction "1_1") (pintype "passive"))
      (node (ref "R2") (pin "1") (pinfunction "1_1") (pintype "passive"))
      (node (ref "R27") (pin "2") (pinfunction "2_2") (pintype "passive"))
      (node (ref "R30") (pin "A") (pinfunction "A_A") (pintype "passive"))
      (node (ref "R31") (pin "A") (pinfunction "A_A") (pintype "passive"))
      (node (ref "R4") (pin "1") (pinfunction "1_1") (pintype "passive"))
      (node (ref "RESETSWITCH") (pin "3") (pinfunction "P_3") (pintype "passive"))
      (node (ref "RESETSWITCH") (pin "4") (pinfunction "P1_4") (pintype "passive"))
      (node (ref "U1") (pin "9") (pinfunction "VSS_9") (pintype "power_in"))
      (node (ref "X2") (pin "1") (pinfunction "1_1") (pintype "passive"))
    )
    (net (code "37") (name "LRXC") (class "Default")
      (node (ref "IC2") (pin "4") (pinfunction "RXD_4") (pintype "output"))
      (node (ref "R19") (pin "2") (pinfunction "2_2") (pintype "passive"))
      (node (ref "U1") (pin "2") (pinfunction "RXCAN_2") (pintype "input"))
    )
    (net (code "38") (name "LTXC") (class "Default")
      (node (ref "IC2") (pin "1") (pinfunction "TXD_1") (pintype "input"))
      (node (ref "R18") (pin "2") (pinfunction "2_2") (pintype "passive"))
      (node (ref "U1") (pin "1") (pinfunction "TXCAN_1") (pintype "output"))
    )
    (net (code "39") (name "ML") (class "Default")
      (node (ref "C10") (pin "2") (pinfunction "2_2") (pintype "passive"))
      (node (ref "SW2") (pin "14") (pinfunction "14_14") (pintype "passive"))
      (node (ref "X2") (pin "2") (pinfunction "2_2") (pintype "passive"))
      (node (ref "X2") (pin "4") (pinfunction "4_4") (pintype "passive"))
    )
    (net (code "40") (name "MR") (class "Default")
      (node (ref "C11") (pin "2") (pinfunction "2_2") (pintype "passive"))
      (node (ref "SW2") (pin "13") (pinfunction "13_13") (pintype "passive"))
      (node (ref "X2") (pin "3") (pinfunction "3_3") (pintype "passive"))
      (node (ref "X2") (pin "5") (pinfunction "5_5") (pintype "passive"))
    )
    (net (code "41") (name "MWRX") (class "Default")
      (node (ref "ESP01") (pin "RX") (pinfunction "RXD0_RX") (pintype "bidirectional"))
      (node (ref "R14") (pin "2") (pinfunction "2_2") (pintype "passive"))
      (node (ref "R26") (pin "2") (pinfunction "2_2") (pintype "passive"))
      (node (ref "R27") (pin "1") (pinfunction "1_1") (pintype "passive"))
      (node (ref "SW4") (pin "5") (pinfunction "5_5") (pintype "passive"))
    )
    (net (code "42") (name "Net-(4XJUMPERS-Pad2)") (class "Default")
      (node (ref "4XJUMPERS") (pin "2") (pinfunction "2_2") (pintype "passive"))
      (node (ref "4XJUMPERS") (pin "4") (pinfunction "4_4") (pintype "passive"))
      (node (ref "COMMPORT1") (pin "2") (pinfunction "2_2") (pintype "passive"))
    )
    (net (code "43") (name "Net-(4XJUMPERS-Pad6)") (class "Default")
      (node (ref "4XJUMPERS") (pin "6") (pinfunction "6_6") (pintype "passive"))
      (node (ref "4XJUMPERS") (pin "8") (pinfunction "8_8") (pintype "passive"))
      (node (ref "COMMPORT1") (pin "3") (pinfunction "3_3") (pintype "passive"))
    )
    (net (code "44") (name "Net-(C4-Pad2)") (class "Default")
      (node (ref "C4") (pin "2") (pinfunction "2_2") (pintype "passive"))
      (node (ref "Q3") (pin "1") (pinfunction "1_1") (pintype "passive"))
      (node (ref "R5") (pin "1") (pinfunction "1_1") (pintype "passive"))
    )
    (net (code "45") (name "Net-(C10-Pad1)") (class "Default")
      (node (ref "C10") (pin "1") (pinfunction "1_1") (pintype "passive"))
      (node (ref "R25") (pin "2") (pinfunction "2_2") (pintype "passive"))
    )
    (net (code "46") (name "Net-(C11-Pad1)") (class "Default")
      (node (ref "C11") (pin "1") (pinfunction "1_1") (pintype "passive"))
      (node (ref "R28") (pin "2") (pinfunction "2_2") (pintype "passive"))
    )
    (net (code "47") (name "Net-(D2--)") (class "Default")
      (node (ref "D2") (pin "2") (pinfunction "-_2") (pintype "passive"))
      (node (ref "R") (pin "1") (pinfunction "1_1") (pintype "passive"))
    )
    (net (code "48") (name "Net-(D3--)") (class "Default")
      (node (ref "D3") (pin "2") (pinfunction "-_2") (pintype "passive"))
      (node (ref "R11") (pin "1") (pinfunction "1_1") (pintype "passive"))
    )
    (net (code "49") (name "Net-(D4--)") (class "Default")
      (node (ref "D4") (pin "2") (pinfunction "-_2") (pintype "passive"))
      (node (ref "R12") (pin "1") (pinfunction "1_1") (pintype "passive"))
    )
    (net (code "50") (name "Net-(D5--)") (class "Default")
      (node (ref "D5") (pin "2") (pinfunction "-_2") (pintype "passive"))
      (node (ref "R13") (pin "1") (pinfunction "1_1") (pintype "passive"))
    )
    (net (code "51") (name "Net-(D6--)") (class "Default")
      (node (ref "D6") (pin "2") (pinfunction "-_2") (pintype "passive"))
      (node (ref "R14") (pin "1") (pinfunction "1_1") (pintype "passive"))
    )
    (net (code "52") (name "Net-(D7--)") (class "Default")
      (node (ref "D7") (pin "2") (pinfunction "-_2") (pintype "passive"))
      (node (ref "R15") (pin "1") (pinfunction "1_1") (pintype "passive"))
    )
    (net (code "53") (name "Net-(D8--)") (class "Default")
      (node (ref "D8") (pin "2") (pinfunction "-_2") (pintype "passive"))
      (node (ref "R16") (pin "1") (pinfunction "1_1") (pintype "passive"))
    )
    (net (code "54") (name "Net-(D9--)") (class "Default")
      (node (ref "D9") (pin "2") (pinfunction "-_2") (pintype "passive"))
      (node (ref "R17") (pin "1") (pinfunction "1_1") (pintype "passive"))
    )
    (net (code "55") (name "Net-(D10--)") (class "Default")
      (node (ref "D10") (pin "2") (pinfunction "-_2") (pintype "passive"))
      (node (ref "R18") (pin "1") (pinfunction "1_1") (pintype "passive"))
    )
    (net (code "56") (name "Net-(D11--)") (class "Default")
      (node (ref "D11") (pin "2") (pinfunction "-_2") (pintype "passive"))
      (node (ref "R19") (pin "1") (pinfunction "1_1") (pintype "passive"))
    )
    (net (code "57") (name "Net-(D12--)") (class "Default")
      (node (ref "D12") (pin "2") (pinfunction "-_2") (pintype "passive"))
      (node (ref "R20") (pin "1") (pinfunction "1_1") (pintype "passive"))
    )
    (net (code "58") (name "Net-(D13--)") (class "Default")
      (node (ref "D13") (pin "2") (pinfunction "-_2") (pintype "passive"))
      (node (ref "R21") (pin "1") (pinfunction "1_1") (pintype "passive"))
    )
    (net (code "59") (name "Net-(D14--)") (class "Default")
      (node (ref "D14") (pin "2") (pinfunction "-_2") (pintype "passive"))
      (node (ref "R22") (pin "1") (pinfunction "1_1") (pintype "passive"))
    )
    (net (code "60") (name "Net-(D15--)") (class "Default")
      (node (ref "D15") (pin "2") (pinfunction "-_2") (pintype "passive"))
      (node (ref "R24") (pin "1") (pinfunction "1_1") (pintype "passive"))
    )
    (net (code "61") (name "Net-(F2-1)") (class "Default")
      (node (ref "F2") (pin "A") (pinfunction "1_A") (pintype "passive"))
      (node (ref "J1") (pin "PWR") (pinfunction "PWR_PWR") (pintype "bidirectional"))
      (node (ref "J7") (pin "1") (pinfunction "1_1") (pintype "passive"))
    )
    (net (code "62") (name "Net-(F2-2)") (class "Default")
      (node (ref "C1") (pin "1") (pinfunction "1_1") (pintype "passive"))
      (node (ref "F2") (pin "B") (pinfunction "2_B") (pintype "passive"))
      (node (ref "IC1") (pin "3") (pinfunction "IN_3") (pintype "input"))
      (node (ref "IC3") (pin "1") (pinfunction "VI_1") (pintype "input"))
    )
    (net (code "63") (name "Net-(IC1-ADJ)") (class "Default")
      (node (ref "IC1") (pin "1") (pinfunction "ADJ_1") (pintype "input"))
      (node (ref "R2") (pin "2") (pinfunction "2_2") (pintype "passive"))
      (node (ref "R3") (pin "1") (pinfunction "1_1") (pintype "passive"))
    )
    (net (code "64") (name "Net-(IC2-CANH)") (class "Default")
      (node (ref "IC2") (pin "7") (pinfunction "CANH_7") (pintype "bidirectional"))
      (node (ref "J10") (pin "1") (pinfunction "1_1") (pintype "passive"))
      (node (ref "J9") (pin "1") (pinfunction "1_1") (pintype "passive"))
      (node (ref "JP1") (pin "1") (pinfunction "1_1") (pintype "passive"))
    )
    (net (code "65") (name "Net-(IC2-CANL)") (class "Default")
      (node (ref "IC2") (pin "6") (pinfunction "CANL_6") (pintype "bidirectional"))
      (node (ref "J10") (pin "2") (pinfunction "2_2") (pintype "passive"))
      (node (ref "J9") (pin "2") (pinfunction "2_2") (pintype "passive"))
      (node (ref "R23") (pin "1") (pinfunction "1_1") (pintype "passive"))
    )
    (net (code "66") (name "Net-(IC3-VO)") (class "Default")
      (node (ref "D1") (pin "A") (pinfunction "A_A") (pintype "passive"))
      (node (ref "IC3") (pin "3") (pinfunction "VO_3") (pintype "passive"))
      (node (ref "LED1") (pin "A") (pinfunction "A_A") (pintype "passive"))
    )
    (net (code "67") (name "Net-(IC5A-C2+-Pad11)") (class "Default")
      (node (ref "IC5") (pin "11") (pinfunction "C2+_11") (pintype "bidirectional"))
      (node (ref "IC5") (pin "15") (pinfunction "C2+_15") (pintype "bidirectional"))
    )
    (net (code "68") (name "Net-(IC5A-C2--Pad10)") (class "Default")
      (node (ref "IC5") (pin "10") (pinfunction "C2-_10") (pintype "bidirectional"))
      (node (ref "IC5") (pin "16") (pinfunction "C2-_16") (pintype "bidirectional"))
    )
    (net (code "69") (name "Net-(IC5A-R1IN)") (class "Default")
      (node (ref "4XJUMPERS") (pin "1") (pinfunction "1_1") (pintype "passive"))
      (node (ref "4XJUMPERS") (pin "7") (pinfunction "7_7") (pintype "passive"))
      (node (ref "IC5") (pin "4") (pinfunction "R1IN_4") (pintype "input"))
    )
    (net (code "70") (name "Net-(IC5A-T1OUT)") (class "Default")
      (node (ref "4XJUMPERS") (pin "3") (pinfunction "3_3") (pintype "passive"))
      (node (ref "4XJUMPERS") (pin "5") (pinfunction "5_5") (pintype "passive"))
      (node (ref "IC5") (pin "5") (pinfunction "T1OUT_5") (pintype "output"))
    )
    (net (code "71") (name "Net-(IC5A-V--Pad12)") (class "Default")
      (node (ref "IC5") (pin "12") (pinfunction "V-_12") (pintype "bidirectional"))
      (node (ref "IC5") (pin "17") (pinfunction "V-_17") (pintype "bidirectional"))
    )
    (net (code "72") (name "Net-(J6-Pad2)") (class "Default")
      (node (ref "J6") (pin "2") (pinfunction "2_2") (pintype "passive"))
      (node (ref "SW2") (pin "7") (pinfunction "7_7") (pintype "passive"))
      (node (ref "SW2") (pin "8") (pinfunction "8_8") (pintype "passive"))
    )
    (net (code "73") (name "Net-(JP1-Pad2)") (class "Default")
      (node (ref "JP1") (pin "2") (pinfunction "2_2") (pintype "passive"))
      (node (ref "R23") (pin "2") (pinfunction "2_2") (pintype "passive"))
    )
    (net (code "74") (name "Net-(LCD-Pad3)") (class "Default")
      (node (ref "LCD") (pin "3") (pinfunction "3_3") (pintype "passive"))
      (node (ref "R30") (pin "S") (pinfunction "S_S") (pintype "passive"))
    )
    (net (code "75") (name "Net-(LCD-Pad15)") (class "Default")
      (node (ref "LCD") (pin "15") (pinfunction "15_15") (pintype "passive"))
      (node (ref "R8") (pin "2") (pinfunction "2_2") (pintype "passive"))
    )
    (net (code "76") (name "Net-(LED1-C)") (class "Default")
      (node (ref "LED1") (pin "K") (pinfunction "C_K") (pintype "passive"))
      (node (ref "R4") (pin "2") (pinfunction "2_2") (pintype "passive"))
    )
    (net (code "77") (name "Net-(LED2-C)") (class "Default")
      (node (ref "LED2") (pin "K") (pinfunction "C_K") (pintype "passive"))
      (node (ref "R1") (pin "2") (pinfunction "2_2") (pintype "passive"))
    )
    (net (code "78") (name "Net-(M1-V+)") (class "Default")
      (node (ref "J11") (pin "2") (pinfunction "2_2") (pintype "passive"))
      (node (ref "JP3") (pin "1") (pinfunction "1_1") (pintype "passive"))
      (node (ref "M1") (pin "2") (pinfunction "V+_2") (pintype "bidirectional"))
      (node (ref "M2") (pin "2") (pinfunction "V+_2") (pintype "bidirectional"))
      (node (ref "M3") (pin "2") (pinfunction "V+_2") (pintype "bidirectional"))
      (node (ref "M4") (pin "2") (pinfunction "V+_2") (pintype "bidirectional"))
      (node (ref "M5") (pin "2") (pinfunction "V+_2") (pintype "bidirectional"))
      (node (ref "M6") (pin "2") (pinfunction "V+_2") (pintype "bidirectional"))
      (node (ref "M7") (pin "2") (pinfunction "V+_2") (pintype "bidirectional"))
      (node (ref "M8") (pin "2") (pinfunction "V+_2") (pintype "bidirectional"))
    )
    (net (code "79") (name "OSC1") (class "Default")
      (node (ref "C3") (pin "2") (pinfunction "2_2") (pintype "passive"))
      (node (ref "J3") (pin "14") (pinfunction "14_14") (pintype "passive"))
      (node (ref "PIC") (pin "13") (pinfunction "OSC1/CLKIN_13") (pintype "input"))
      (node (ref "Q3") (pin "2") (pinfunction "2_2") (pintype "passive"))
    )
    (net (code "80") (name "OSC2") (class "Default")
      (node (ref "J3") (pin "13") (pinfunction "13_13") (pintype "passive"))
      (node (ref "PIC") (pin "14") (pinfunction "OSC2/CLKOUT_14") (pintype "output"))
      (node (ref "R5") (pin "2") (pinfunction "2_2") (pintype "passive"))
    )
    (net (code "81") (name "OSC3") (class "Default")
      (node (ref "C5") (pin "1") (pinfunction "1_1") (pintype "passive"))
      (node (ref "Q4") (pin "2") (pinfunction "2_2") (pintype "passive"))
      (node (ref "U1") (pin "7") (pinfunction "OSC2_7") (pintype "output"))
    )
    (net (code "82") (name "OSC4") (class "Default")
      (node (ref "C6") (pin "1") (pinfunction "1_1") (pintype "passive"))
      (node (ref "Q4") (pin "1") (pinfunction "1_1") (pintype "passive"))
      (node (ref "U1") (pin "8") (pinfunction "OSC1_8") (pintype "input"))
    )
    (net (code "83") (name "P0") (class "Default")
      (node (ref "J5") (pin "21") (pinfunction "21_21") (pintype "passive"))
      (node (ref "SW2") (pin "3") (pinfunction "3_3") (pintype "passive"))
      (node (ref "SW2") (pin "4") (pinfunction "4_4") (pintype "passive"))
    )
    (net (code "84") (name "P1") (class "Default")
      (node (ref "J5") (pin "16") (pinfunction "16_16") (pintype "passive"))
      (node (ref "SW2") (pin "10") (pinfunction "10_10") (pintype "passive"))
    )
    (net (code "85") (name "P2") (class "Default")
      (node (ref "J5") (pin "10") (pinfunction "10_10") (pintype "passive"))
    )
    (net (code "86") (name "P3") (class "Default")
      (node (ref "J5") (pin "22") (pinfunction "22_22") (pintype "passive"))
    )
    (net (code "87") (name "P4") (class "Default")
      (node (ref "J5") (pin "20") (pinfunction "20_20") (pintype "passive"))
    )
    (net (code "88") (name "P5") (class "Default")
      (node (ref "J5") (pin "19") (pinfunction "19_19") (pintype "passive"))
    )
    (net (code "89") (name "P6") (class "Default")
      (node (ref "J5") (pin "18") (pinfunction "18_18") (pintype "passive"))
    )
    (net (code "90") (name "P7") (class "Default")
      (node (ref "J5") (pin "17") (pinfunction "17_17") (pintype "passive"))
    )
    (net (code "91") (name "P8") (class "Default")
      (node (ref "J5") (pin "15") (pinfunction "15_15") (pintype "passive"))
    )
    (net (code "92") (name "P9") (class "Default")
      (node (ref "J5") (pin "14") (pinfunction "14_14") (pintype "passive"))
    )
    (net (code "93") (name "P10") (class "Default")
      (node (ref "J5") (pin "13") (pinfunction "13_13") (pintype "passive"))
    )
    (net (code "94") (name "P11") (class "Default")
      (node (ref "J5") (pin "12") (pinfunction "12_12") (pintype "passive"))
    )
    (net (code "95") (name "P12") (class "Default")
      (node (ref "J5") (pin "11") (pinfunction "11_11") (pintype "passive"))
    )
    (net (code "96") (name "P13") (class "Default")
      (node (ref "J5") (pin "9") (pinfunction "9_9") (pintype "passive"))
      (node (ref "SW4") (pin "12") (pinfunction "12_12") (pintype "passive"))
    )
    (net (code "97") (name "P14") (class "Default")
      (node (ref "J5") (pin "8") (pinfunction "8_8") (pintype "passive"))
      (node (ref "SW4") (pin "13") (pinfunction "13_13") (pintype "passive"))
    )
    (net (code "98") (name "P15") (class "Default")
      (node (ref "J5") (pin "7") (pinfunction "7_7") (pintype "passive"))
      (node (ref "SW2") (pin "16") (pinfunction "16_16") (pintype "passive"))
    )
    (net (code "99") (name "P16") (class "Default")
      (node (ref "J5") (pin "6") (pinfunction "6_6") (pintype "passive"))
      (node (ref "SW2") (pin "15") (pinfunction "15_15") (pintype "passive"))
    )
    (net (code "100") (name "PBRX") (class "Default")
      (node (ref "J12") (pin "4") (pinfunction "4_4") (pintype "passive"))
      (node (ref "SW4") (pin "10") (pinfunction "10_10") (pintype "passive"))
    )
    (net (code "101") (name "PBTX") (class "Default")
      (node (ref "J12") (pin "3") (pinfunction "3_3") (pintype "passive"))
      (node (ref "SW4") (pin "11") (pinfunction "11_11") (pintype "passive"))
    )
    (net (code "102") (name "PL") (class "Default")
      (node (ref "R25") (pin "1") (pinfunction "1_1") (pintype "passive"))
      (node (ref "SW2") (pin "12") (pinfunction "12_12") (pintype "passive"))
    )
    (net (code "103") (name "PMRX") (class "Default")
      (node (ref "R10") (pin "2") (pinfunction "2_2") (pintype "passive"))
      (node (ref "R9") (pin "1") (pinfunction "1_1") (pintype "passive"))
      (node (ref "SW2") (pin "2") (pinfunction "2_2") (pintype "passive"))
    )
    (net (code "104") (name "PR") (class "Default")
      (node (ref "R28") (pin "1") (pinfunction "1_1") (pintype "passive"))
      (node (ref "SW2") (pin "11") (pinfunction "11_11") (pintype "passive"))
    )
    (net (code "105") (name "PWRX") (class "Default")
      (node (ref "R26") (pin "1") (pinfunction "1_1") (pintype "passive"))
      (node (ref "SW4") (pin "16") (pinfunction "16_16") (pintype "passive"))
    )
    (net (code "106") (name "PWTX") (class "Default")
      (node (ref "ESP01") (pin "TX") (pinfunction "TXD0_TX") (pintype "bidirectional"))
      (node (ref "R15") (pin "2") (pinfunction "2_2") (pintype "passive"))
      (node (ref "SW4") (pin "15") (pinfunction "15_15") (pintype "passive"))
      (node (ref "SW4") (pin "4") (pinfunction "4_4") (pintype "passive"))
    )
    (net (code "107") (name "RESET") (class "Default")
      (node (ref "J2") (pin "6") (pinfunction "6_6") (pintype "passive"))
      (node (ref "J3") (pin "1") (pinfunction "1_1") (pintype "passive"))
      (node (ref "PIC") (pin "1") (pinfunction "~{MCLR/THV}_1") (pintype "input"))
      (node (ref "R6") (pin "1") (pinfunction "1_1") (pintype "passive"))
      (node (ref "RESETSWITCH") (pin "1") (pinfunction "S_1") (pintype "passive"))
      (node (ref "RESETSWITCH") (pin "2") (pinfunction "S1_2") (pintype "passive"))
      (node (ref "U1") (pin "17") (pinfunction "RESET_17") (pintype "input"))
    )
    (net (code "108") (name "VCC") (class "Default")
      (node (ref "C2") (pin "1") (pinfunction "1_1") (pintype "passive"))
      (node (ref "C7") (pin "1") (pinfunction "1_1") (pintype "passive"))
      (node (ref "C8") (pin "2") (pinfunction "2_2") (pintype "passive"))
      (node (ref "C9") (pin "2") (pinfunction "2_2") (pintype "passive"))
      (node (ref "D1") (pin "C") (pinfunction "C_C") (pintype "passive"))
      (node (ref "D10") (pin "1") (pinfunction "+_1") (pintype "passive"))
      (node (ref "D11") (pin "1") (pinfunction "+_1") (pintype "passive"))
      (node (ref "D12") (pin "1") (pinfunction "+_1") (pintype "passive"))
      (node (ref "D13") (pin "1") (pinfunction "+_1") (pintype "passive"))
      (node (ref "D14") (pin "1") (pinfunction "+_1") (pintype "passive"))
      (node (ref "D15") (pin "1") (pinfunction "+_1") (pintype "passive"))
      (node (ref "D2") (pin "1") (pinfunction "+_1") (pintype "passive"))
      (node (ref "D3") (pin "1") (pinfunction "+_1") (pintype "passive"))
      (node (ref "D4") (pin "1") (pinfunction "+_1") (pintype "passive"))
      (node (ref "D5") (pin "1") (pinfunction "+_1") (pintype "passive"))
      (node (ref "D6") (pin "1") (pinfunction "+_1") (pintype "passive"))
      (node (ref "D7") (pin "1") (pinfunction "+_1") (pintype "passive"))
      (node (ref "D8") (pin "1") (pinfunction "+_1") (pintype "passive"))
      (node (ref "D9") (pin "1") (pinfunction "+_1") (pintype "passive"))
      (node (ref "IC2") (pin "3") (pinfunction "VCC_3") (pintype "power_in"))
      (node (ref "IC5") (pin "7") (pinfunction "VCC_7") (pintype "power_in"))
      (node (ref "J12") (pin "1") (pinfunction "1_1") (pintype "passive"))
      (node (ref "J2") (pin "5") (pinfunction "5_5") (pintype "passive"))
      (node (ref "J3") (pin "11") (pinfunction "11_11") (pintype "passive"))
      (node (ref "J3") (pin "32") (pinfunction "32_32") (pintype "passive"))
      (node (ref "J6") (pin "3") (pinfunction "3_3") (pintype "passive"))
      (node (ref "JP3") (pin "2") (pinfunction "2_2") (pintype "passive"))
      (node (ref "LCD") (pin "2") (pinfunction "2_2") (pintype "passive"))
      (node (ref "PIC") (pin "11") (pinfunction "VDD_11") (pintype "power_in"))
      (node (ref "PIC") (pin "32") (pinfunction "VDD_32") (pintype "power_in"))
      (node (ref "R30") (pin "E") (pinfunction "E_E") (pintype "passive"))
      (node (ref "R31") (pin "E") (pinfunction "E_E") (pintype "passive"))
      (node (ref "R6") (pin "2") (pinfunction "2_2") (pintype "passive"))
      (node (ref "R7") (pin "2") (pinfunction "2_2") (pintype "passive"))
      (node (ref "R8") (pin "1") (pinfunction "1_1") (pintype "passive"))
      (node (ref "U1") (pin "18") (pinfunction "VDD_18") (pintype "power_in"))
    )
    (net (code "109") (name "W3.3V") (class "Default")
      (node (ref "ESP01") (pin "3V3") (pinfunction "3.3V_3V3") (pintype "passive"))
      (node (ref "ESP01") (pin "EN/CH_PD") (pinfunction "EN/CHPD_EN/CH_PD") (pintype "bidirectional"))
      (node (ref "SW4") (pin "3") (pinfunction "3_3") (pintype "passive"))
    )
    (net (code "110") (name "unconnected-(COMMPORT1-Pad1)") (class "Default")
      (node (ref "COMMPORT1") (pin "1") (pinfunction "1_1") (pintype "passive"))
    )
    (net (code "111") (name "unconnected-(COMMPORT1-Pad4)") (class "Default")
      (node (ref "COMMPORT1") (pin "4") (pinfunction "4_4") (pintype "passive"))
    )
    (net (code "112") (name "unconnected-(COMMPORT1-Pad6)") (class "Default")
      (node (ref "COMMPORT1") (pin "6") (pinfunction "6_6") (pintype "passive"))
    )
    (net (code "113") (name "unconnected-(COMMPORT1-Pad7)") (class "Default")
      (node (ref "COMMPORT1") (pin "7") (pinfunction "7_7") (pintype "passive"))
    )
    (net (code "114") (name "unconnected-(COMMPORT1-Pad8)") (class "Default")
      (node (ref "COMMPORT1") (pin "8") (pinfunction "8_8") (pintype "passive"))
    )
    (net (code "115") (name "unconnected-(COMMPORT1-Pad9)") (class "Default")
      (node (ref "COMMPORT1") (pin "9") (pinfunction "9_9") (pintype "passive"))
    )
    (net (code "116") (name "unconnected-(ESP01-PadGPIO0)") (class "Default")
      (node (ref "ESP01") (pin "GPIO0") (pinfunction "GPIO0_GPIO0") (pintype "bidirectional"))
    )
    (net (code "117") (name "unconnected-(ESP01-PadGPIO2)") (class "Default")
      (node (ref "ESP01") (pin "GPIO2") (pinfunction "GPIO2_GPIO2") (pintype "bidirectional"))
    )
    (net (code "118") (name "unconnected-(ESP01-~{RST}-PadRST)") (class "Default")
      (node (ref "ESP01") (pin "RST") (pinfunction "~{RST}_RST") (pintype "bidirectional"))
    )
    (net (code "119") (name "unconnected-(IC2-VREF-Pad5)") (class "Default")
      (node (ref "IC2") (pin "5") (pinfunction "VREF_5") (pintype "output"))
    )
    (net (code "120") (name "unconnected-(IC5A-C1+-Pad8)") (class "Default")
      (node (ref "IC5") (pin "8") (pinfunction "C1+_8") (pintype "bidirectional"))
    )
    (net (code "121") (name "unconnected-(IC5A-C1--Pad13)") (class "Default")
      (node (ref "IC5") (pin "13") (pinfunction "C1-_13") (pintype "bidirectional"))
    )
    (net (code "122") (name "unconnected-(IC5A-R2IN-Pad19)") (class "Default")
      (node (ref "IC5") (pin "19") (pinfunction "R2IN_19") (pintype "input"))
    )
    (net (code "123") (name "unconnected-(IC5A-R2OUT-Pad20)") (class "Default")
      (node (ref "IC5") (pin "20") (pinfunction "R2OUT_20") (pintype "output"))
    )
    (net (code "124") (name "unconnected-(IC5A-T2IN-Pad1)") (class "Default")
      (node (ref "IC5") (pin "1") (pinfunction "T2IN_1") (pintype "input"))
    )
    (net (code "125") (name "unconnected-(IC5A-T2OUT-Pad18)") (class "Default")
      (node (ref "IC5") (pin "18") (pinfunction "T2OUT_18") (pintype "output"))
    )
    (net (code "126") (name "unconnected-(IC5A-V+-Pad14)") (class "Default")
      (node (ref "IC5") (pin "14") (pinfunction "V+_14") (pintype "bidirectional"))
    )
    (net (code "127") (name "unconnected-(U1A-CLKOUT-Pad3)") (class "Default")
      (node (ref "U1") (pin "3") (pinfunction "CLKOUT_3") (pintype "output"))
    )
    (net (code "128") (name "unconnected-(U1A-RX0BF-Pad11)") (class "Default")
      (node (ref "U1") (pin "11") (pinfunction "RX0BF_11") (pintype "output"))
    )
    (net (code "129") (name "unconnected-(U1A-RX1BF-Pad10)") (class "Default")
      (node (ref "U1") (pin "10") (pinfunction "RX1BF_10") (pintype "output"))
    )
    (net (code "130") (name "unconnected-(U1A-TX0RTS-Pad4)") (class "Default")
      (node (ref "U1") (pin "4") (pinfunction "TX0RTS_4") (pintype "input"))
    )
    (net (code "131") (name "unconnected-(U1A-TX1RTS-Pad5)") (class "Default")
      (node (ref "U1") (pin "5") (pinfunction "TX1RTS_5") (pintype "input"))
    )
    (net (code "132") (name "unconnected-(U1A-TX2RTS-Pad6)") (class "Default")
      (node (ref "U1") (pin "6") (pinfunction "TX2RTS_6") (pintype "input"))
    )
  )
)
